# DAC.net
KiCad netlist of a schematic drawn in Altium Designer
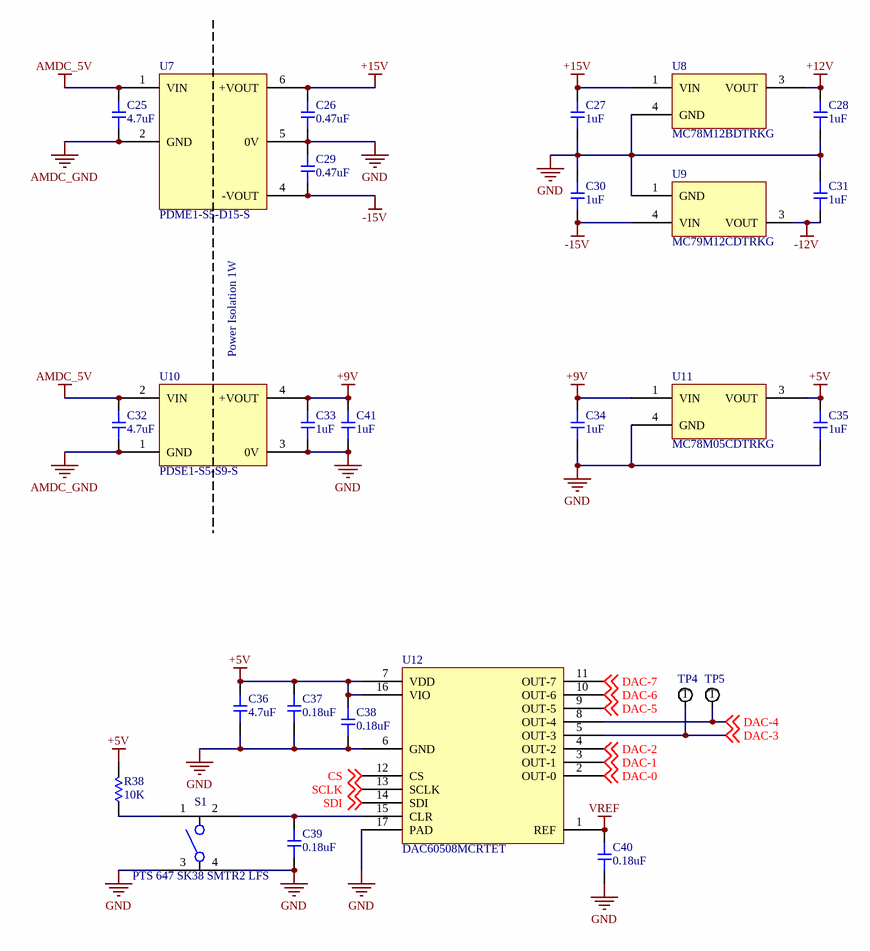
[diagram p0: DAC.SchDoc]

(export (version "E")
  (design (tool "Eeschema 10.0.6"))
  (components
    (comp (ref "C25")
      (value "4.7uF")
      (footprint "0603-CAP")
      (description "4.7µF ±10% 25V Ceramic Capacitor X5R 0603 (1608 Metric)")
      (fields (field (name "Comment") "CL10A475KA8NQNC"))
      (libsource (lib "DAC") (part "Capacitor 4.7uF"))
    )
    (comp (ref "C26")
      (value "0.47uF")
      (footprint "0603-CAP")
      (description "0.47µF ±10% 16V Ceramic Capacitor X7R 0603 (1608 Metric)")
      (fields (field (name "Comment") "CL10B474KO8NNNC"))
      (libsource (lib "DAC") (part "Capacitor .47uF"))
    )
    (comp (ref "C27")
      (value "1uF")
      (footprint "0603-CAP")
      (description "1µF ±10% 10V Ceramic Capacitor X5R 0603 (1608 Metric)")
      (fields (field (name "Comment") "CL10A105KP8NNNC"))
      (libsource (lib "DAC") (part "Capacitor 1uF"))
    )
    (comp (ref "C28")
      (value "1uF")
      (footprint "0603-CAP")
      (description "1µF ±10% 10V Ceramic Capacitor X5R 0603 (1608 Metric)")
      (fields (field (name "Comment") "CL10A105KP8NNNC"))
      (libsource (lib "DAC") (part "Capacitor 1uF"))
    )
    (comp (ref "C29")
      (value "0.47uF")
      (footprint "0603-CAP")
      (description "0.47µF ±10% 16V Ceramic Capacitor X7R 0603 (1608 Metric)")
      (fields (field (name "Comment") "CL10B474KO8NNNC"))
      (libsource (lib "DAC") (part "Capacitor .47uF"))
    )
    (comp (ref "C30")
      (value "1uF")
      (footprint "0603-CAP")
      (description "1µF ±10% 10V Ceramic Capacitor X5R 0603 (1608 Metric)")
      (fields (field (name "Comment") "CL10A105KP8NNNC"))
      (libsource (lib "DAC") (part "Capacitor 1uF"))
    )
    (comp (ref "C31")
      (value "1uF")
      (footprint "0603-CAP")
      (description "1µF ±10% 10V Ceramic Capacitor X5R 0603 (1608 Metric)")
      (fields (field (name "Comment") "CL10A105KP8NNNC"))
      (libsource (lib "DAC") (part "Capacitor 1uF"))
    )
    (comp (ref "C32")
      (value "4.7uF")
      (footprint "0603-CAP")
      (description "4.7µF ±10% 25V Ceramic Capacitor X5R 0603 (1608 Metric)")
      (fields (field (name "Comment") "CL10A475KA8NQNC"))
      (libsource (lib "DAC") (part "Capacitor 4.7uF"))
    )
    (comp (ref "C33")
      (value "1uF")
      (footprint "0603-CAP")
      (description "1µF ±10% 10V Ceramic Capacitor X5R 0603 (1608 Metric)")
      (fields (field (name "Comment") "CL10A105KP8NNNC"))
      (libsource (lib "DAC") (part "Capacitor 1uF"))
    )
    (comp (ref "C34")
      (value "1uF")
      (footprint "0603-CAP")
      (description "1µF ±10% 10V Ceramic Capacitor X5R 0603 (1608 Metric)")
      (fields (field (name "Comment") "CL10A105KP8NNNC"))
      (libsource (lib "DAC") (part "Capacitor 1uF"))
    )
    (comp (ref "C35")
      (value "1uF")
      (footprint "0603-CAP")
      (description "1µF ±10% 10V Ceramic Capacitor X5R 0603 (1608 Metric)")
      (fields (field (name "Comment") "CL10A105KP8NNNC"))
      (libsource (lib "DAC") (part "Capacitor 1uF"))
    )
    (comp (ref "C36")
      (value "4.7uF")
      (footprint "0603-CAP")
      (description "4.7µF ±10% 25V Ceramic Capacitor X5R 0603 (1608 Metric)")
      (fields (field (name "Comment") "CL10A475KA8NQNC"))
      (libsource (lib "DAC") (part "Capacitor 4.7uF"))
    )
    (comp (ref "C37")
      (value "0.18uF")
      (footprint "0603-CAP")
      (description "0.18µF ±10% 16V Ceramic Capacitor X7R 0603 (1608 Metric)")
      (fields (field (name "Comment") "CC0603KRX7R7BB184"))
      (libsource (lib "DAC") (part "Capacitor 0.18uF"))
    )
    (comp (ref "C38")
      (value "0.18uF")
      (footprint "0603-CAP")
      (description "0.18µF ±10% 16V Ceramic Capacitor X7R 0603 (1608 Metric)")
      (fields (field (name "Comment") "CC0603KRX7R7BB184"))
      (libsource (lib "DAC") (part "Capacitor 0.18uF"))
    )
    (comp (ref "C39")
      (value "0.18uF")
      (footprint "0603-CAP")
      (description "0.18µF ±10% 16V Ceramic Capacitor X7R 0603 (1608 Metric)")
      (fields (field (name "Comment") "CC0603KRX7R7BB184"))
      (libsource (lib "DAC") (part "Capacitor 0.18uF"))
    )
    (comp (ref "C40")
      (value "0.18uF")
      (footprint "0603-CAP")
      (description "0.18µF ±10% 16V Ceramic Capacitor X7R 0603 (1608 Metric)")
      (fields (field (name "Comment") "CC0603KRX7R7BB184"))
      (libsource (lib "DAC") (part "Capacitor 0.18uF"))
    )
    (comp (ref "C41")
      (value "1uF")
      (footprint "0603-CAP")
      (description "1µF ±10% 10V Ceramic Capacitor X5R 0603 (1608 Metric)")
      (fields (field (name "Comment") "CL10A105KP8NNNC"))
      (libsource (lib "DAC") (part "Capacitor 1uF"))
    )
    (comp (ref "R38")
      (value "10K")
      (footprint "0603-RES")
      (fields (field (name "Comment") "ERJ-PB3B1002V"))
      (libsource (lib "DAC") (part "Resistor 10K"))
    )
    (comp (ref "S1")
      (value "PTS 647 SK38 SMTR2 LFS")
      (footprint "PTS647SK38SMTR2LFSCT-ND")
      (description "Tactile Switch SPST-NO Top Actuated Surface Mount")
      (libsource (lib "DAC") (part "PTS 647 SK38 SMTR2 LFS"))
    )
    (comp (ref "TP4") (value "Test Point") (footprint "RCU-0C") (libsource (lib "DAC") (part "Test Point")))
    (comp (ref "TP5") (value "Test Point") (footprint "RCU-0C") (libsource (lib "DAC") (part "Test Point")))
    (comp (ref "U7")
      (value "PDME1-S5-D15-S")
      (footprint "PDME1-S5-D15-S")
      (description "Isolated Module DC DC Converter 2 Output 15V -15V   34mA, 34mA 4.5V - 5.5V Input")
      (libsource (lib "DAC") (part "PDME1-S5-D15-S"))
    )
    (comp (ref "U8")
      (value "MC78M12BDTRKG")
      (footprint "DPAK229P991X238-3N")
      (description "+12 Linear Voltage Regulator IC  1 Output  500mA DPAK")
      (libsource (lib "DAC") (part "MC78M12BDTRKG"))
    )
    (comp (ref "U9")
      (value "MC79M12CDTRKG")
      (footprint "DPAK229P991X238-3N")
      (description "-12 Linear Voltage Regulator IC  1 Output  500mA DPAK")
      (libsource (lib "DAC") (part "MC79M12CDTRKG"))
    )
    (comp (ref "U10")
      (value "PDSE1-S5-S9-S")
      (footprint "PDSE1-S5-S9-S")
      (description "Isolated Module DC DC Converter 1 Output 9V    111mA 4.5V - 5.5V Input")
      (libsource (lib "DAC") (part "PDSE1-S5-S9-S"))
    )
    (comp (ref "U11")
      (value "MC78M05CDTRKG")
      (footprint "DPAK229P991X238-3N")
      (description "+5V Linear Voltage Regulator IC  1 Output  500mA DPAK")
      (libsource (lib "DAC") (part "MC78M05CDTRKG"))
    )
    (comp (ref "U12")
      (value "DAC60508MCRTET")
      (footprint "QFN50P300X300X80_HS-17N")
      (description "12 Bit Digital to Analog Converter 8 16-WQFN (3x3)")
      (libsource (lib "DAC") (part "DAC60508MCRTET"))
    )
  )
  (nets
    (net (code "1") (name "+5V") (class "Default")
      (node (ref "C35") (pin "2") (pinfunction "2_2") (pintype "passive"))
      (node (ref "C36") (pin "2") (pinfunction "2_2") (pintype "passive"))
      (node (ref "C37") (pin "2") (pinfunction "2_2") (pintype "passive"))
      (node (ref "C38") (pin "2") (pinfunction "2_2") (pintype "passive"))
      (node (ref "R38") (pin "2") (pinfunction "2_2") (pintype "passive"))
      (node (ref "U11") (pin "3") (pinfunction "VOUT_3") (pintype "passive"))
      (node (ref "U12") (pin "16") (pinfunction "VIO_16") (pintype "passive"))
      (node (ref "U12") (pin "7") (pinfunction "VDD_7") (pintype "passive"))
    )
    (net (code "2") (name "+9V") (class "Default")
      (node (ref "C33") (pin "2") (pinfunction "2_2") (pintype "passive"))
      (node (ref "C34") (pin "2") (pinfunction "2_2") (pintype "passive"))
      (node (ref "C41") (pin "2") (pinfunction "2_2") (pintype "passive"))
      (node (ref "U10") (pin "4") (pinfunction "+VOUT_4") (pintype "passive"))
      (node (ref "U11") (pin "1") (pinfunction "VIN_1") (pintype "passive"))
    )
    (net (code "3") (name "+12V") (class "Default")
      (node (ref "C28") (pin "2") (pinfunction "2_2") (pintype "passive"))
      (node (ref "U8") (pin "3") (pinfunction "VOUT_3") (pintype "passive"))
    )
    (net (code "4") (name "+15V") (class "Default")
      (node (ref "C26") (pin "2") (pinfunction "2_2") (pintype "passive"))
      (node (ref "C27") (pin "2") (pinfunction "2_2") (pintype "passive"))
      (node (ref "U7") (pin "6") (pinfunction "+VOUT_6") (pintype "passive"))
      (node (ref "U8") (pin "1") (pinfunction "VIN_1") (pintype "passive"))
    )
    (net (code "5") (name "-12V") (class "Default")
      (node (ref "C31") (pin "1") (pinfunction "1_1") (pintype "passive"))
      (node (ref "U9") (pin "3") (pinfunction "VOUT_3") (pintype "passive"))
    )
    (net (code "6") (name "-15V") (class "Default")
      (node (ref "C29") (pin "1") (pinfunction "1_1") (pintype "passive"))
      (node (ref "C30") (pin "1") (pinfunction "1_1") (pintype "passive"))
      (node (ref "U7") (pin "4") (pinfunction "-VOUT_4") (pintype "passive"))
      (node (ref "U9") (pin "4") (pinfunction "VIN_4") (pintype "passive"))
    )
    (net (code "7") (name "AMDC_5V") (class "Default")
      (node (ref "C25") (pin "2") (pinfunction "2_2") (pintype "passive"))
      (node (ref "C32") (pin "2") (pinfunction "2_2") (pintype "passive"))
      (node (ref "U10") (pin "2") (pinfunction "VIN_2") (pintype "passive"))
      (node (ref "U7") (pin "1") (pinfunction "VIN_1") (pintype "passive"))
    )
    (net (code "8") (name "AMDC_GND") (class "Default")
      (node (ref "C25") (pin "1") (pinfunction "1_1") (pintype "passive"))
      (node (ref "C32") (pin "1") (pinfunction "1_1") (pintype "passive"))
      (node (ref "U10") (pin "1") (pinfunction "GND_1") (pintype "passive"))
      (node (ref "U7") (pin "2") (pinfunction "GND_2") (pintype "passive"))
    )
    (net (code "9") (name "CS") (class "Default")
      (node (ref "U12") (pin "12") (pinfunction "CS_12") (pintype "passive"))
    )
    (net (code "10") (name "DAC-0") (class "Default")
      (node (ref "U12") (pin "2") (pinfunction "OUT-0_2") (pintype "passive"))
    )
    (net (code "11") (name "DAC-1") (class "Default")
      (node (ref "U12") (pin "3") (pinfunction "OUT-1_3") (pintype "passive"))
    )
    (net (code "12") (name "DAC-2") (class "Default")
      (node (ref "U12") (pin "4") (pinfunction "OUT-2_4") (pintype "passive"))
    )
    (net (code "13") (name "DAC-3") (class "Default")
      (node (ref "TP4") (pin "1") (pinfunction "1_1") (pintype "passive"))
      (node (ref "U12") (pin "5") (pinfunction "OUT-3_5") (pintype "passive"))
    )
    (net (code "14") (name "DAC-4") (class "Default")
      (node (ref "TP5") (pin "1") (pinfunction "1_1") (pintype "passive"))
      (node (ref "U12") (pin "8") (pinfunction "OUT-4_8") (pintype "passive"))
    )
    (net (code "15") (name "DAC-5") (class "Default")
      (node (ref "U12") (pin "9") (pinfunction "OUT-5_9") (pintype "passive"))
    )
    (net (code "16") (name "DAC-6") (class "Default")
      (node (ref "U12") (pin "10") (pinfunction "OUT-6_10") (pintype "passive"))
    )
    (net (code "17") (name "DAC-7") (class "Default")
      (node (ref "U12") (pin "11") (pinfunction "OUT-7_11") (pintype "passive"))
    )
    (net (code "18") (name "GND") (class "Default")
      (node (ref "C26") (pin "1") (pinfunction "1_1") (pintype "passive"))
      (node (ref "C27") (pin "1") (pinfunction "1_1") (pintype "passive"))
      (node (ref "C28") (pin "1") (pinfunction "1_1") (pintype "passive"))
      (node (ref "C29") (pin "2") (pinfunction "2_2") (pintype "passive"))
      (node (ref "C30") (pin "2") (pinfunction "2_2") (pintype "passive"))
      (node (ref "C31") (pin "2") (pinfunction "2_2") (pintype "passive"))
      (node (ref "C33") (pin "1") (pinfunction "1_1") (pintype "passive"))
      (node (ref "C34") (pin "1") (pinfunction "1_1") (pintype "passive"))
      (node (ref "C35") (pin "1") (pinfunction "1_1") (pintype "passive"))
      (node (ref "C36") (pin "1") (pinfunction "1_1") (pintype "passive"))
      (node (ref "C37") (pin "1") (pinfunction "1_1") (pintype "passive"))
      (node (ref "C38") (pin "1") (pinfunction "1_1") (pintype "passive"))
      (node (ref "C39") (pin "1") (pinfunction "1_1") (pintype "passive"))
      (node (ref "C40") (pin "1") (pinfunction "1_1") (pintype "passive"))
      (node (ref "C41") (pin "1") (pinfunction "1_1") (pintype "passive"))
      (node (ref "S1") (pin "3") (pintype "passive"))
      (node (ref "S1") (pin "4") (pintype "passive"))
      (node (ref "U10") (pin "3") (pinfunction "0V_3") (pintype "passive"))
      (node (ref "U11") (pin "4") (pinfunction "GND_4") (pintype "passive"))
      (node (ref "U12") (pin "17") (pinfunction "PAD_17") (pintype "passive"))
      (node (ref "U12") (pin "6") (pinfunction "GND_6") (pintype "passive"))
      (node (ref "U7") (pin "5") (pinfunction "0V_5") (pintype "passive"))
      (node (ref "U8") (pin "4") (pinfunction "GND_4") (pintype "passive"))
      (node (ref "U9") (pin "1") (pinfunction "GND_1") (pintype "passive"))
    )
    (net (code "19") (name "Net-(R38-Pad1)") (class "Default")
      (node (ref "R38") (pin "1") (pinfunction "1_1") (pintype "passive"))
      (node (ref "S1") (pin "1") (pintype "passive"))
    )
    (net (code "20") (name "Net-(U12-CLR)") (class "Default")
      (node (ref "C39") (pin "2") (pinfunction "2_2") (pintype "passive"))
      (node (ref "S1") (pin "2") (pintype "passive"))
      (node (ref "U12") (pin "15") (pinfunction "CLR_15") (pintype "passive"))
    )
    (net (code "21") (name "SCLK") (class "Default")
      (node (ref "U12") (pin "13") (pinfunction "SCLK_13") (pintype "passive"))
    )
    (net (code "22") (name "SDI") (class "Default")
      (node (ref "U12") (pin "14") (pinfunction "SDI_14") (pintype "passive"))
    )
    (net (code "23") (name "VREF") (class "Default")
      (node (ref "C40") (pin "2") (pinfunction "2_2") (pintype "passive"))
      (node (ref "U12") (pin "1") (pinfunction "REF_1") (pintype "passive"))
    )
  )
)
